# sdi-master.net
KiCad netlist of a schematic drawn in EAGLE
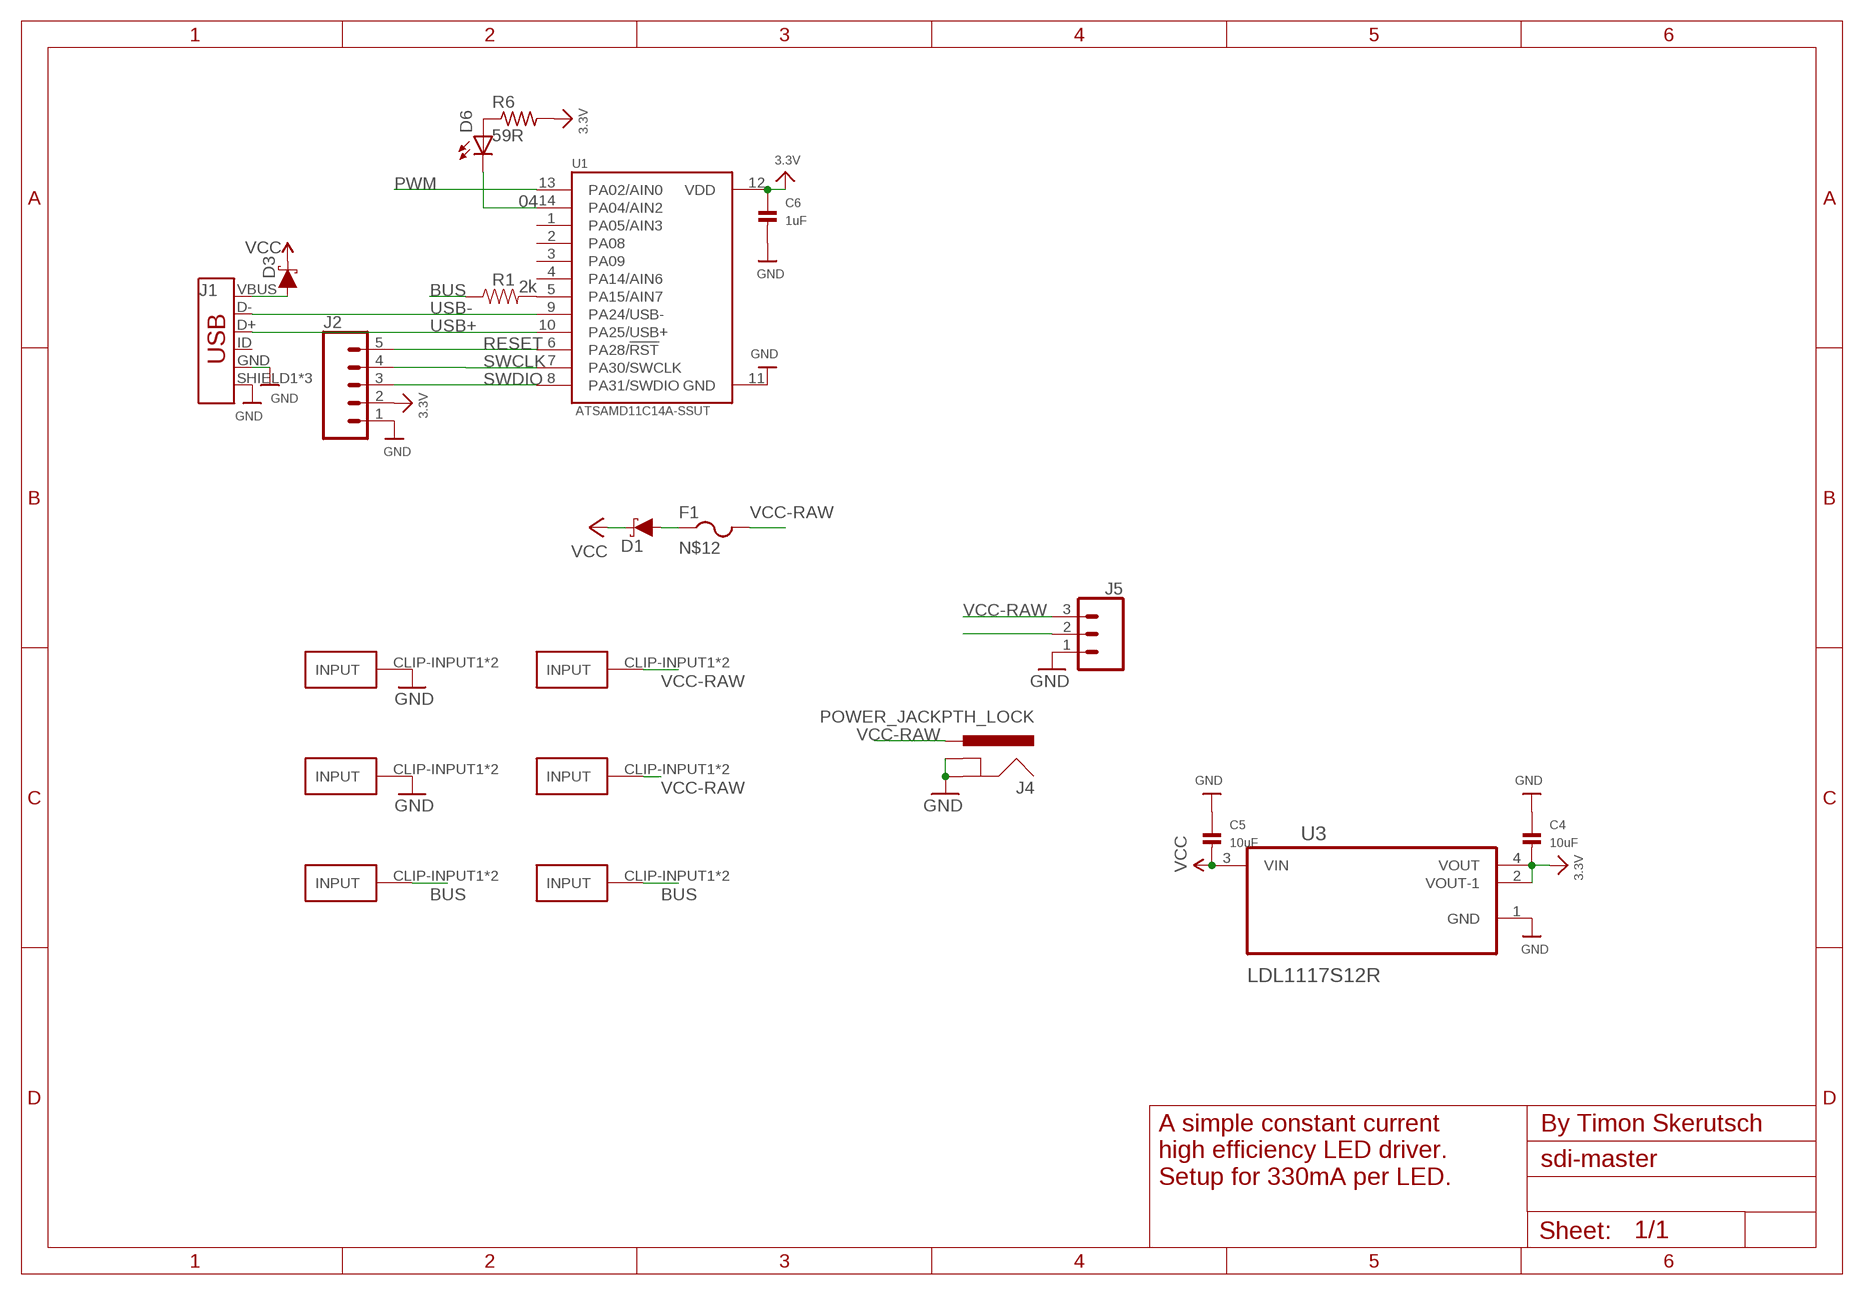
[diagram p0: schematic, sheet 1]

(export (version "E")
  (design (tool "Eeschema 10.0.6"))
  (components
    (comp (ref "C4")
      (value "10uF")
      (footprint "eagle-import:0805")
      (libsource (lib "eagle-import") (part "CAP_CERAMIC0805"))
    )
    (comp (ref "C5")
      (value "10uF")
      (footprint "eagle-import:0603")
      (libsource (lib "eagle-import") (part "CAP_CERAMIC0603"))
    )
    (comp (ref "C6")
      (value "1uF")
      (footprint "eagle-import:0603")
      (libsource (lib "eagle-import") (part "CAP_CERAMIC0603"))
    )
    (comp (ref "D1")
      (value "3A/40V/500mV")
      (footprint "eagle-import:SMA-DIODE")
      (libsource (lib "eagle-import") (part "DIODE-SCHOTTKY-B340A"))
    )
    (comp (ref "D3")
      (value "3A/40V/500mV")
      (footprint "eagle-import:SMA-DIODE")
      (libsource (lib "eagle-import") (part "DIODE-SCHOTTKY-B340A"))
    )
    (comp (ref "D6")
      (value "LEDCHIPLED_0805")
      (footprint "eagle-import:CHIPLED_0805")
      (libsource (lib "eagle-import") (part "LEDCHIPLED_0805"))
    )
    (comp (ref "F1")
      (value "TLC-MSMD110/24")
      (footprint "eagle-import:1812")
      (libsource (lib "eagle-import") (part "PTCFUSE-1812"))
    )
    (comp (ref "GND-CLIP")
      (value "FUSE-HOLDER-5X20MM")
      (footprint "eagle-import:FUSE-HOLDER-5X20MM")
      (libsource (lib "eagle-import") (part "FUSE-HOLDER-5X20MM"))
    )
    (comp (ref "GND-CLIP3")
      (value "FUSE-HOLDER-5X20MM")
      (footprint "eagle-import:FUSE-HOLDER-5X20MM")
      (libsource (lib "eagle-import") (part "FUSE-HOLDER-5X20MM"))
    )
    (comp (ref "J1")
      (value "USB_MICRO-B_FEMALE-SMT")
      (footprint "eagle-import:USB-B-MICRO-SMD")
      (libsource (lib "eagle-import") (part "USB_MICRO-B_FEMALE-SMT"))
    )
    (comp (ref "J2")
      (value "CONN_05")
      (footprint "eagle-import:1X05")
      (libsource (lib "eagle-import") (part "CONN_05"))
    )
    (comp (ref "J4")
      (value "POWER_JACKPTH_LOCK")
      (footprint "eagle-import:POWER_JACK_PTH_LOCK")
      (libsource (lib "eagle-import") (part "POWER_JACKPTH_LOCK"))
    )
    (comp (ref "J5")
      (value "CONN_03SCREW-NS")
      (footprint "eagle-import:SCREWTERMINAL-3.5MM-3-NS")
      (libsource (lib "eagle-import") (part "CONN_03SCREW-NS"))
    )
    (comp (ref "PWM-CLIP")
      (value "FUSE-HOLDER-5X20MM")
      (footprint "eagle-import:FUSE-HOLDER-5X20MM")
      (libsource (lib "eagle-import") (part "FUSE-HOLDER-5X20MM"))
    )
    (comp (ref "PWM-CLIP1")
      (value "FUSE-HOLDER-5X20MM")
      (footprint "eagle-import:FUSE-HOLDER-5X20MM")
      (libsource (lib "eagle-import") (part "FUSE-HOLDER-5X20MM"))
    )
    (comp (ref "R1")
      (value "2k")
      (footprint "eagle-import:1206")
      (libsource (lib "eagle-import") (part "RESISTOR1206"))
    )
    (comp (ref "R6")
      (value "59R")
      (footprint "eagle-import:R0805")
      (libsource (lib "eagle-import") (part "R-US_R0805"))
    )
    (comp (ref "U1")
      (value "ATSAMD11C14A-SSUT")
      (footprint "eagle-import:SOIC127P600X160-14N")
      (fields (field (name "MF") "Microchip"))
      (libsource (lib "eagle-import") (part "ATSAMD11C14A-SSUT"))
    )
    (comp (ref "U3")
      (value "LDL1117S12R")
      (footprint "eagle-import:SOT230P700X180-4N")
      (fields (field (name "MF") "STMicroelectronics"))
      (libsource (lib "eagle-import") (part "LDL1117S12R"))
    )
    (comp (ref "VCC-CLIP")
      (value "FUSE-HOLDER-5X20MM")
      (footprint "eagle-import:FUSE-HOLDER-5X20MM")
      (libsource (lib "eagle-import") (part "FUSE-HOLDER-5X20MM"))
    )
    (comp (ref "VCC-CLIP3")
      (value "FUSE-HOLDER-5X20MM")
      (footprint "eagle-import:FUSE-HOLDER-5X20MM")
      (libsource (lib "eagle-import") (part "FUSE-HOLDER-5X20MM"))
    )
  )
  (nets
    (net (code "1") (name "/04") (class "Default")
      (node (ref "D6") (pin "C") (pinfunction "C_C") (pintype "passive"))
      (node (ref "U1") (pin "14") (pinfunction "PA04/AIN2_14") (pintype "bidirectional"))
    )
    (net (code "2") (name "/BUS") (class "Default")
      (node (ref "J5") (pin "2") (pinfunction "2_2") (pintype "passive"))
      (node (ref "PWM-CLIP") (pin "CLIP-INPUT1") (pinfunction "INPUT_CLIP-INPUT1") (pintype "bidirectional"))
      (node (ref "PWM-CLIP") (pin "CLIP-INPUT2") (pinfunction "INPUT_CLIP-INPUT2") (pintype "bidirectional"))
      (node (ref "PWM-CLIP1") (pin "CLIP-INPUT1") (pinfunction "INPUT_CLIP-INPUT1") (pintype "bidirectional"))
      (node (ref "PWM-CLIP1") (pin "CLIP-INPUT2") (pinfunction "INPUT_CLIP-INPUT2") (pintype "bidirectional"))
      (node (ref "R1") (pin "1") (pinfunction "1_1") (pintype "passive"))
    )
    (net (code "3") (name "/N$12") (class "Default")
      (node (ref "D1") (pin "A") (pinfunction "A_A") (pintype "passive"))
      (node (ref "F1") (pin "1") (pinfunction "1_1") (pintype "passive"))
    )
    (net (code "4") (name "/PWM") (class "Default")
      (node (ref "U1") (pin "13") (pinfunction "PA02/AIN0_13") (pintype "bidirectional"))
    )
    (net (code "5") (name "/RESET") (class "Default")
      (node (ref "J2") (pin "5") (pinfunction "5_5") (pintype "passive"))
      (node (ref "U1") (pin "6") (pinfunction "PA28/~{RST}_6") (pintype "bidirectional"))
    )
    (net (code "6") (name "/SWCLK") (class "Default")
      (node (ref "J2") (pin "4") (pinfunction "4_4") (pintype "passive"))
      (node (ref "U1") (pin "7") (pinfunction "PA30/SWCLK_7") (pintype "bidirectional"))
    )
    (net (code "7") (name "/SWDIO") (class "Default")
      (node (ref "J2") (pin "3") (pinfunction "3_3") (pintype "passive"))
      (node (ref "U1") (pin "8") (pinfunction "PA31/SWDIO_8") (pintype "bidirectional"))
    )
    (net (code "8") (name "/USB+") (class "Default")
      (node (ref "J1") (pin "D+") (pinfunction "D+_D+") (pintype "bidirectional"))
      (node (ref "U1") (pin "10") (pinfunction "PA25/USB+_10") (pintype "bidirectional"))
    )
    (net (code "9") (name "/USB-") (class "Default")
      (node (ref "J1") (pin "D-") (pinfunction "D-_D-") (pintype "bidirectional"))
      (node (ref "U1") (pin "9") (pinfunction "PA24/USB-_9") (pintype "bidirectional"))
    )
    (net (code "10") (name "/VCC-RAW") (class "Default")
      (node (ref "F1") (pin "2") (pinfunction "2_2") (pintype "passive"))
      (node (ref "J4") (pin "PWR") (pinfunction "PWR_PWR") (pintype "bidirectional"))
      (node (ref "J5") (pin "3") (pinfunction "3_3") (pintype "passive"))
      (node (ref "VCC-CLIP") (pin "CLIP-INPUT1") (pinfunction "INPUT_CLIP-INPUT1") (pintype "bidirectional"))
      (node (ref "VCC-CLIP") (pin "CLIP-INPUT2") (pinfunction "INPUT_CLIP-INPUT2") (pintype "bidirectional"))
      (node (ref "VCC-CLIP3") (pin "CLIP-INPUT1") (pinfunction "INPUT_CLIP-INPUT1") (pintype "bidirectional"))
      (node (ref "VCC-CLIP3") (pin "CLIP-INPUT2") (pinfunction "INPUT_CLIP-INPUT2") (pintype "bidirectional"))
    )
    (net (code "11") (name "3.3V") (class "Default")
      (node (ref "C4") (pin "2") (pinfunction "P$2_2") (pintype "passive"))
      (node (ref "C6") (pin "1") (pinfunction "P$1_1") (pintype "passive"))
      (node (ref "J2") (pin "2") (pinfunction "2_2") (pintype "passive"))
      (node (ref "R6") (pin "2") (pinfunction "2_2") (pintype "passive"))
      (node (ref "U1") (pin "12") (pinfunction "VDD_12") (pintype "power_in"))
      (node (ref "U3") (pin "2") (pinfunction "VOUT-1_2") (pintype "output"))
      (node (ref "U3") (pin "4") (pinfunction "VOUT_4") (pintype "output"))
    )
    (net (code "12") (name "GND") (class "Default")
      (node (ref "C4") (pin "1") (pinfunction "P$1_1") (pintype "passive"))
      (node (ref "C5") (pin "1") (pinfunction "P$1_1") (pintype "passive"))
      (node (ref "C6") (pin "2") (pinfunction "P$2_2") (pintype "passive"))
      (node (ref "GND-CLIP") (pin "CLIP-INPUT1") (pinfunction "INPUT_CLIP-INPUT1") (pintype "bidirectional"))
      (node (ref "GND-CLIP") (pin "CLIP-INPUT2") (pinfunction "INPUT_CLIP-INPUT2") (pintype "bidirectional"))
      (node (ref "GND-CLIP3") (pin "CLIP-INPUT1") (pinfunction "INPUT_CLIP-INPUT1") (pintype "bidirectional"))
      (node (ref "GND-CLIP3") (pin "CLIP-INPUT2") (pinfunction "INPUT_CLIP-INPUT2") (pintype "bidirectional"))
      (node (ref "J1") (pin "GND") (pinfunction "GND_GND") (pintype "power_in"))
      (node (ref "J1") (pin "SHIELD1") (pinfunction "SHIELD_SHIELD1") (pintype "bidirectional"))
      (node (ref "J1") (pin "SHIELD2") (pinfunction "SHIELD_SHIELD2") (pintype "bidirectional"))
      (node (ref "J1") (pin "SHIELD3") (pinfunction "SHIELD_SHIELD3") (pintype "bidirectional"))
      (node (ref "J2") (pin "1") (pinfunction "1_1") (pintype "passive"))
      (node (ref "J4") (pin "GND") (pinfunction "GND_GND") (pintype "bidirectional"))
      (node (ref "J4") (pin "GNDBREAK") (pinfunction "GNDBREAK_GNDBREAK") (pintype "bidirectional"))
      (node (ref "J5") (pin "1") (pinfunction "1_1") (pintype "passive"))
      (node (ref "U1") (pin "11") (pinfunction "GND_11") (pintype "power_in"))
      (node (ref "U3") (pin "1") (pinfunction "GND_1") (pintype "power_in"))
    )
    (net (code "13") (name "Net-(D3-PadA)") (class "Default")
      (node (ref "D3") (pin "A") (pinfunction "A_A") (pintype "passive"))
      (node (ref "J1") (pin "VBUS") (pinfunction "VBUS_VBUS") (pintype "power_in"))
    )
    (net (code "14") (name "Net-(D6-PadA)") (class "Default")
      (node (ref "D6") (pin "A") (pinfunction "A_A") (pintype "passive"))
      (node (ref "R6") (pin "1") (pinfunction "1_1") (pintype "passive"))
    )
    (net (code "15") (name "Net-(U1-PA15{slash}AIN7)") (class "Default")
      (node (ref "R1") (pin "2") (pinfunction "2_2") (pintype "passive"))
      (node (ref "U1") (pin "5") (pinfunction "PA15/AIN7_5") (pintype "bidirectional"))
    )
    (net (code "16") (name "VCC") (class "Default")
      (node (ref "C5") (pin "2") (pinfunction "P$2_2") (pintype "passive"))
      (node (ref "D1") (pin "C") (pinfunction "C_C") (pintype "passive"))
      (node (ref "D3") (pin "C") (pinfunction "C_C") (pintype "passive"))
      (node (ref "U3") (pin "3") (pinfunction "VIN_3") (pintype "input"))
    )
    (net (code "17") (name "unconnected-(J1-PadID)") (class "Default")
      (node (ref "J1") (pin "ID") (pinfunction "ID_ID") (pintype "bidirectional"))
    )
    (net (code "18") (name "unconnected-(U1-PA05{slash}AIN3-Pad1)") (class "Default")
      (node (ref "U1") (pin "1") (pinfunction "PA05/AIN3_1") (pintype "bidirectional"))
    )
    (net (code "19") (name "unconnected-(U1-PA08-Pad2)") (class "Default")
      (node (ref "U1") (pin "2") (pinfunction "PA08_2") (pintype "bidirectional"))
    )
    (net (code "20") (name "unconnected-(U1-PA09-Pad3)") (class "Default")
      (node (ref "U1") (pin "3") (pinfunction "PA09_3") (pintype "bidirectional"))
    )
    (net (code "21") (name "unconnected-(U1-PA14{slash}AIN6-Pad4)") (class "Default")
      (node (ref "U1") (pin "4") (pinfunction "PA14/AIN6_4") (pintype "bidirectional"))
    )
  )
)
